# battery_brick_2_12.net
KiCad netlist of a schematic drawn in EAGLE
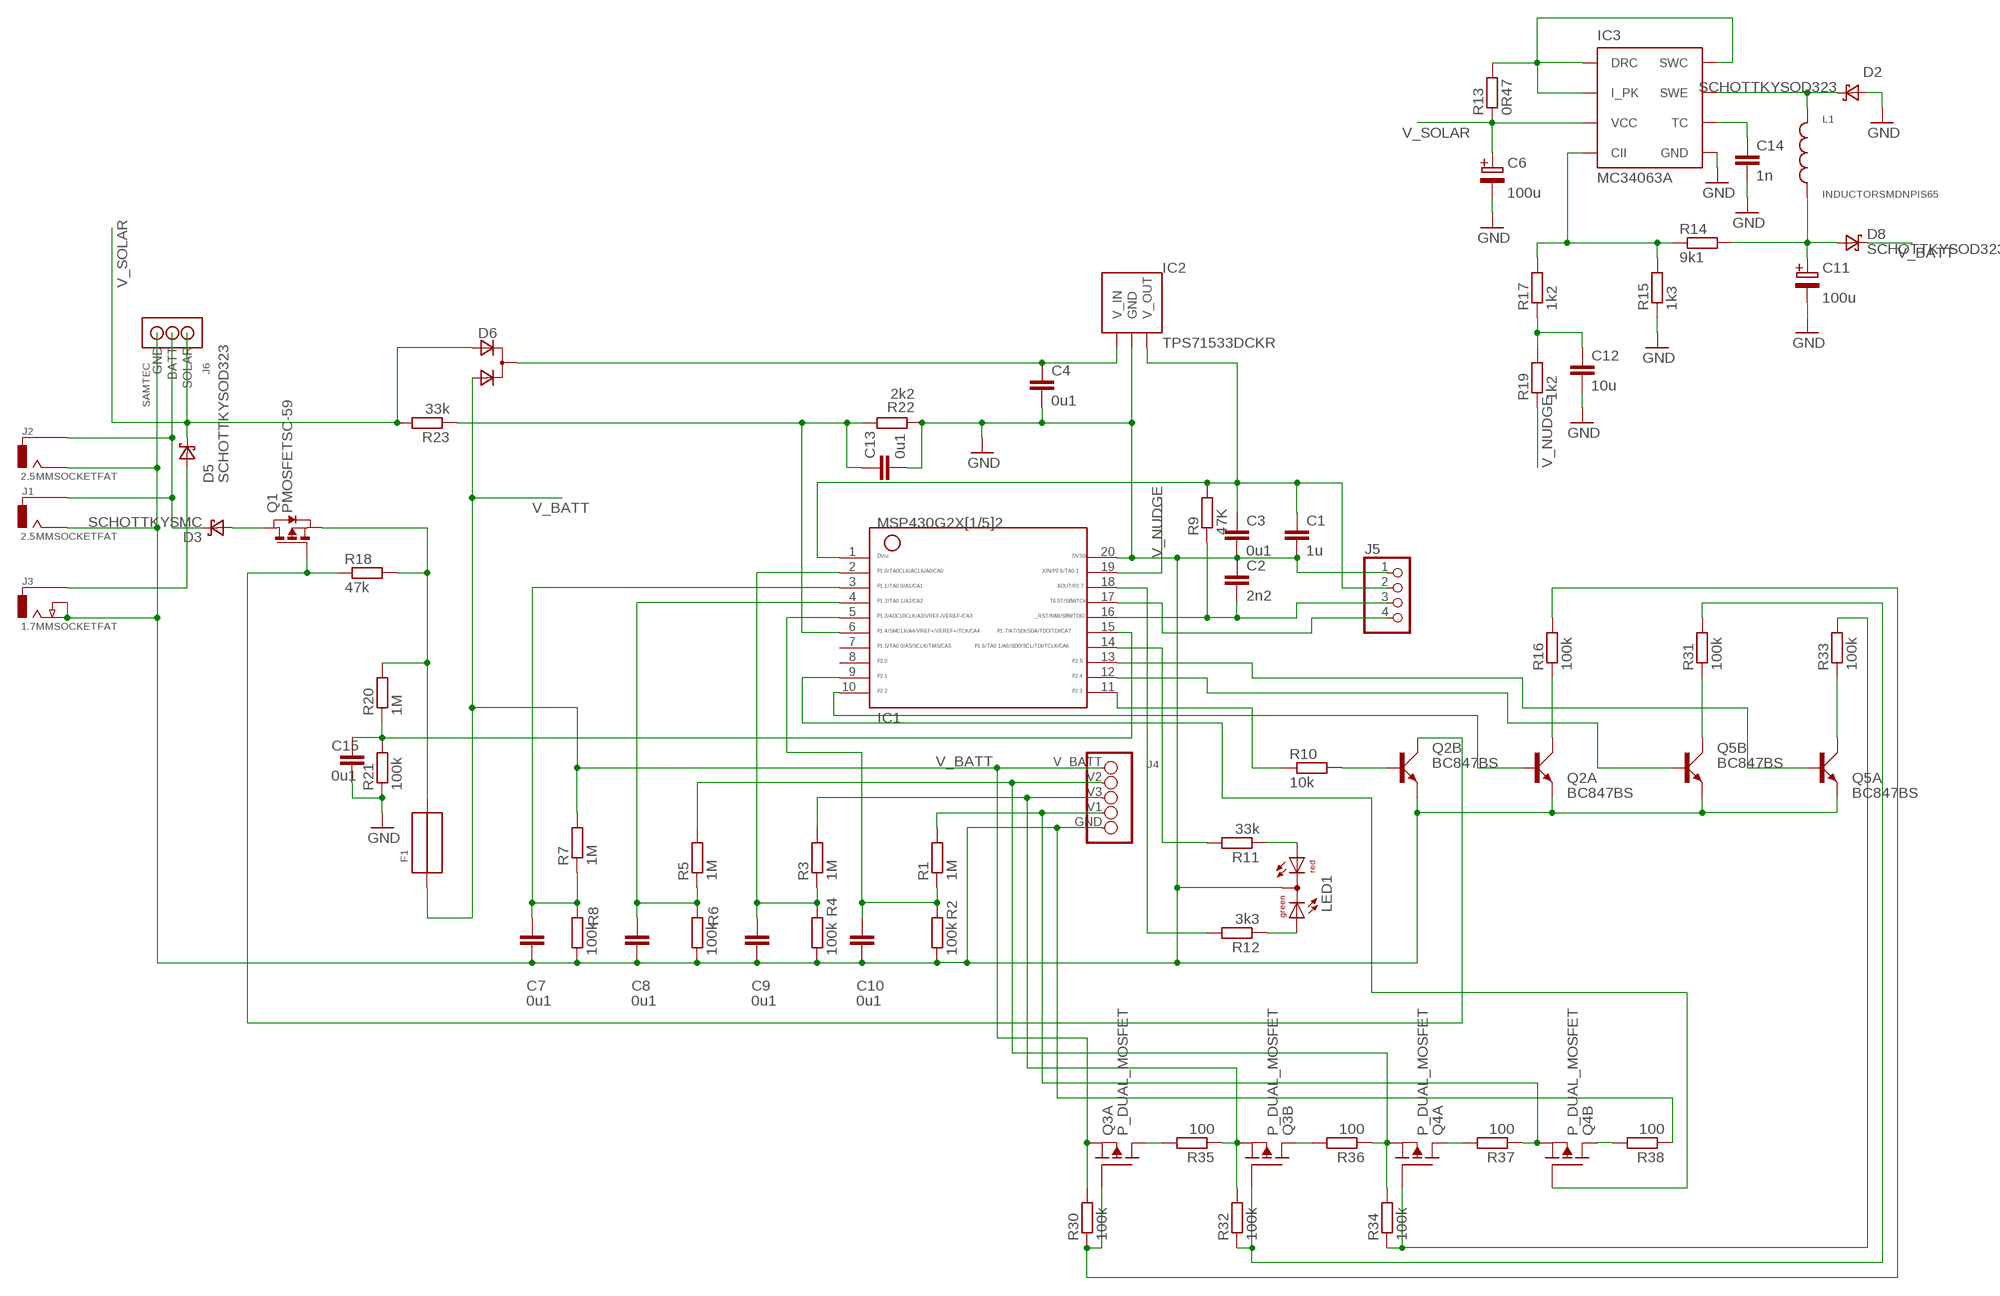
[diagram p0: schematic, sheet 1]

(export (version "E")
  (design (tool "Eeschema 10.0.6"))
  (components
    (comp (ref "C1")
      (value "1u")
      (footprint "eagle-import:C0603K")
      (libsource (lib "eagle-import") (part "C-EUC0603K"))
    )
    (comp (ref "C2")
      (value "2n2")
      (footprint "eagle-import:C0603K")
      (libsource (lib "eagle-import") (part "C-EUC0603K"))
    )
    (comp (ref "C3")
      (value "0u1")
      (footprint "eagle-import:C0603K")
      (libsource (lib "eagle-import") (part "C-EUC0603K"))
    )
    (comp (ref "C4")
      (value "0u1")
      (footprint "eagle-import:C0603")
      (libsource (lib "eagle-import") (part "C-EUC0603"))
    )
    (comp (ref "C6")
      (value "100u")
      (footprint "eagle-import:CAPCANVZH101")
      (libsource (lib "eagle-import") (part "ELEC_CAP_CAN6VZH101"))
    )
    (comp (ref "C7")
      (value "0u1")
      (footprint "eagle-import:C0603")
      (libsource (lib "eagle-import") (part "C-EUC0603"))
    )
    (comp (ref "C8")
      (value "0u1")
      (footprint "eagle-import:C0603")
      (libsource (lib "eagle-import") (part "C-EUC0603"))
    )
    (comp (ref "C9")
      (value "0u1")
      (footprint "eagle-import:C0603")
      (libsource (lib "eagle-import") (part "C-EUC0603"))
    )
    (comp (ref "C10")
      (value "0u1")
      (footprint "eagle-import:C0603")
      (libsource (lib "eagle-import") (part "C-EUC0603"))
    )
    (comp (ref "C11")
      (value "100u")
      (footprint "eagle-import:CAPCANVZH101")
      (libsource (lib "eagle-import") (part "ELEC_CAP_CAN6VZH101"))
    )
    (comp (ref "C12")
      (value "10u")
      (footprint "eagle-import:C2012")
      (libsource (lib "eagle-import") (part "C-EUC2012"))
    )
    (comp (ref "C13")
      (value "0u1")
      (footprint "eagle-import:C0603")
      (libsource (lib "eagle-import") (part "C-EUC0603"))
    )
    (comp (ref "C14")
      (value "1n")
      (footprint "eagle-import:C0603")
      (libsource (lib "eagle-import") (part "C-EUC0603"))
    )
    (comp (ref "C15")
      (value "0u1")
      (footprint "eagle-import:C0603")
      (libsource (lib "eagle-import") (part "C-EUC0603"))
    )
    (comp (ref "D2")
      (value "SCHOTTKYSOD323")
      (footprint "eagle-import:SOD323")
      (libsource (lib "eagle-import") (part "SCHOTTKYSOD323"))
    )
    (comp (ref "D3")
      (value "SCHOTTKYSMC")
      (footprint "eagle-import:SMC")
      (libsource (lib "eagle-import") (part "SCHOTTKYSMC"))
    )
    (comp (ref "D5")
      (value "SCHOTTKYSOD323")
      (footprint "eagle-import:SOD323")
      (libsource (lib "eagle-import") (part "SCHOTTKYSOD323"))
    )
    (comp (ref "D6")
      (value "D_2ASOT323")
      (footprint "eagle-import:SOT323")
      (libsource (lib "eagle-import") (part "D_2ASOT323"))
    )
    (comp (ref "D8")
      (value "SCHOTTKYSOD323")
      (footprint "eagle-import:SOD323")
      (libsource (lib "eagle-import") (part "SCHOTTKYSOD323"))
    )
    (comp (ref "F1")
      (value "FUSE")
      (footprint "eagle-import:1812")
      (libsource (lib "eagle-import") (part "FUSE"))
    )
    (comp (ref "IC1")
      (value "G2X[1/5]2---PW20")
      (footprint "eagle-import:PW20")
      (libsource (lib "eagle-import") (part "G2X[1/5]2---PW20"))
    )
    (comp (ref "IC2")
      (value "TPS71533DCKR")
      (footprint "eagle-import:SC70-5")
      (libsource (lib "eagle-import") (part "TPS71533DCKR"))
    )
    (comp (ref "IC3")
      (value "MC34063A")
      (footprint "eagle-import:SOIC8")
      (libsource (lib "eagle-import") (part "MC34063A"))
    )
    (comp (ref "J1")
      (value "2.5MMSOCKETFAT")
      (footprint "eagle-import:2.5MMSOCKET-OBLONGFAT")
      (libsource (lib "eagle-import") (part "2.5MMSOCKETFAT"))
    )
    (comp (ref "J2")
      (value "2.5MMSOCKETFAT")
      (footprint "eagle-import:2.5MMSOCKET-OBLONGFAT")
      (libsource (lib "eagle-import") (part "2.5MMSOCKETFAT"))
    )
    (comp (ref "J3")
      (value "1.7MMSOCKETFAT")
      (footprint "eagle-import:1.7MMSOCKET-OBLONGFAT")
      (libsource (lib "eagle-import") (part "1.7MMSOCKETFAT"))
    )
    (comp (ref "J4")
      (value "S5B-PH-K-S")
      (footprint "eagle-import:S5B-PH-K-S")
      (libsource (lib "eagle-import") (part "S5B-PH-K-S"))
    )
    (comp (ref "J5")
      (value "PINHD-1X4")
      (footprint "eagle-import:1X04")
      (libsource (lib "eagle-import") (part "PINHD-1X4"))
    )
    (comp (ref "J6")
      (value "SAMTEC")
      (footprint "eagle-import:SAMTEC")
      (libsource (lib "eagle-import") (part "SAMTEC"))
    )
    (comp (ref "L1")
      (value "INDUCTORSMDNPIS65")
      (footprint "eagle-import:INDUCTOR_NPIS65")
      (libsource (lib "eagle-import") (part "INDUCTORSMDNPIS65"))
    )
    (comp (ref "LED1")
      (value "DUOLED5MM")
      (footprint "eagle-import:DUOLED5MM")
      (libsource (lib "eagle-import") (part "DUOLED5MM"))
    )
    (comp (ref "Q1")
      (value "PMOSFETSC-59")
      (footprint "eagle-import:SC-59")
      (libsource (lib "eagle-import") (part "PMOSFETSC-59"))
    )
    (comp (ref "Q2")
      (value "BC847BS")
      (footprint "eagle-import:SOT363_PHILIPS")
      (libsource (lib "eagle-import") (part "BC847BS"))
    )
    (comp (ref "Q3")
      (value "P_DUAL_MOSFET")
      (footprint "eagle-import:SOT666")
      (libsource (lib "eagle-import") (part "P_DUAL_MOSFET"))
    )
    (comp (ref "Q4")
      (value "P_DUAL_MOSFET")
      (footprint "eagle-import:SOT666")
      (libsource (lib "eagle-import") (part "P_DUAL_MOSFET"))
    )
    (comp (ref "Q5")
      (value "BC847BS")
      (footprint "eagle-import:SOT363_PHILIPS")
      (libsource (lib "eagle-import") (part "BC847BS"))
    )
    (comp (ref "R1")
      (value "1M")
      (footprint "eagle-import:R0805")
      (libsource (lib "eagle-import") (part "R-EU_R0805"))
    )
    (comp (ref "R2")
      (value "100k")
      (footprint "eagle-import:R0805")
      (libsource (lib "eagle-import") (part "resistor_R-EU_R0805"))
    )
    (comp (ref "R3")
      (value "1M")
      (footprint "eagle-import:R0805")
      (libsource (lib "eagle-import") (part "R-EU_R0805"))
    )
    (comp (ref "R4")
      (value "100k")
      (footprint "eagle-import:R0805")
      (libsource (lib "eagle-import") (part "resistor_R-EU_R0805"))
    )
    (comp (ref "R5")
      (value "1M")
      (footprint "eagle-import:R0805")
      (libsource (lib "eagle-import") (part "R-EU_R0805"))
    )
    (comp (ref "R6")
      (value "100k")
      (footprint "eagle-import:R0805")
      (libsource (lib "eagle-import") (part "resistor_R-EU_R0805"))
    )
    (comp (ref "R7")
      (value "1M")
      (footprint "eagle-import:R0805")
      (libsource (lib "eagle-import") (part "R-EU_R0805"))
    )
    (comp (ref "R8")
      (value "100k")
      (footprint "eagle-import:R0805")
      (libsource (lib "eagle-import") (part "resistor_R-EU_R0805"))
    )
    (comp (ref "R9")
      (value "47K")
      (footprint "eagle-import:R0603")
      (libsource (lib "eagle-import") (part "R-EU_R0603"))
    )
    (comp (ref "R10")
      (value "10k")
      (footprint "eagle-import:R0603")
      (libsource (lib "eagle-import") (part "R-EU_R0603"))
    )
    (comp (ref "R11")
      (value "33k")
      (footprint "eagle-import:R0603")
      (libsource (lib "eagle-import") (part "resistor_R-EU_R0603"))
    )
    (comp (ref "R12")
      (value "3k3")
      (footprint "eagle-import:R0603")
      (libsource (lib "eagle-import") (part "resistor_R-EU_R0603"))
    )
    (comp (ref "R13")
      (value "0R47")
      (footprint "eagle-import:R1206")
      (libsource (lib "eagle-import") (part "R-EU_R1206"))
    )
    (comp (ref "R14")
      (value "9k1")
      (footprint "eagle-import:R0603")
      (libsource (lib "eagle-import") (part "R-EU_R0603"))
    )
    (comp (ref "R15")
      (value "1k3")
      (footprint "eagle-import:R0603")
      (libsource (lib "eagle-import") (part "R-EU_R0603"))
    )
    (comp (ref "R16")
      (value "100k")
      (footprint "eagle-import:R0603")
      (libsource (lib "eagle-import") (part "resistor_R-EU_R0603"))
    )
    (comp (ref "R17")
      (value "1k2")
      (footprint "eagle-import:R0603")
      (libsource (lib "eagle-import") (part "R-EU_R0603"))
    )
    (comp (ref "R18")
      (value "47k")
      (footprint "eagle-import:R0603")
      (libsource (lib "eagle-import") (part "R-EU_R0603"))
    )
    (comp (ref "R19")
      (value "1k2")
      (footprint "eagle-import:R0603")
      (libsource (lib "eagle-import") (part "R-EU_R0603"))
    )
    (comp (ref "R20")
      (value "1M")
      (footprint "eagle-import:R0603")
      (libsource (lib "eagle-import") (part "R-EU_R0603"))
    )
    (comp (ref "R21")
      (value "100k")
      (footprint "eagle-import:R0603")
      (libsource (lib "eagle-import") (part "resistor_R-EU_R0603"))
    )
    (comp (ref "R22")
      (value "2k2")
      (footprint "eagle-import:R0603")
      (libsource (lib "eagle-import") (part "resistor_R-EU_R0603"))
    )
    (comp (ref "R23")
      (value "33k")
      (footprint "eagle-import:R0603")
      (libsource (lib "eagle-import") (part "resistor_R-EU_R0603"))
    )
    (comp (ref "R30")
      (value "100k")
      (footprint "eagle-import:R0603")
      (libsource (lib "eagle-import") (part "resistor_R-EU_R0603"))
    )
    (comp (ref "R31")
      (value "100k")
      (footprint "eagle-import:R0603")
      (libsource (lib "eagle-import") (part "resistor_R-EU_R0603"))
    )
    (comp (ref "R32")
      (value "100k")
      (footprint "eagle-import:R0603")
      (libsource (lib "eagle-import") (part "resistor_R-EU_R0603"))
    )
    (comp (ref "R33")
      (value "100k")
      (footprint "eagle-import:R0603")
      (libsource (lib "eagle-import") (part "resistor_R-EU_R0603"))
    )
    (comp (ref "R34")
      (value "100k")
      (footprint "eagle-import:R0603")
      (libsource (lib "eagle-import") (part "resistor_R-EU_R0603"))
    )
    (comp (ref "R35")
      (value "100")
      (footprint "eagle-import:M1206")
      (libsource (lib "eagle-import") (part "R-EU_M1206"))
    )
    (comp (ref "R36")
      (value "100")
      (footprint "eagle-import:M1206")
      (libsource (lib "eagle-import") (part "R-EU_M1206"))
    )
    (comp (ref "R37")
      (value "100")
      (footprint "eagle-import:M1206")
      (libsource (lib "eagle-import") (part "R-EU_M1206"))
    )
    (comp (ref "R38")
      (value "100")
      (footprint "eagle-import:M1206")
      (libsource (lib "eagle-import") (part "R-EU_M1206"))
    )
  )
  (nets
    (net (code "1") (name "/V_BATT") (class "Default")
      (node (ref "D6") (pin "3") (pinfunction "A2_3") (pintype "passive"))
      (node (ref "D8") (pin "CATHODE") (pinfunction "CATHODE_CATHODE") (pintype "passive"))
      (node (ref "F1") (pin "1") (pinfunction "P$1_1") (pintype "bidirectional"))
      (node (ref "J4") (pin "V_BATT") (pinfunction "V_BATT_V_BATT") (pintype "input"))
      (node (ref "Q3") (pin "1") (pinfunction "S_1") (pintype "passive"))
      (node (ref "R30") (pin "2") (pinfunction "2_2") (pintype "passive"))
      (node (ref "R7") (pin "2") (pinfunction "2_2") (pintype "passive"))
    )
    (net (code "2") (name "/V_NUDGE") (class "Default")
      (node (ref "IC1") (pin "19") (pinfunction "19_19") (pintype "bidirectional"))
      (node (ref "R19") (pin "1") (pinfunction "1_1") (pintype "passive"))
    )
    (net (code "3") (name "/V_SOLAR") (class "Default")
      (node (ref "C6") (pin "+VE") (pinfunction "P$1+_+VE") (pintype "bidirectional"))
      (node (ref "D5") (pin "CATHODE") (pinfunction "CATHODE_CATHODE") (pintype "passive"))
      (node (ref "D6") (pin "2") (pinfunction "A1_2") (pintype "passive"))
      (node (ref "IC3") (pin "VCC") (pinfunction "VCC_VCC") (pintype "input"))
      (node (ref "J6") (pin "SOLAR") (pinfunction "SOLAR_SOLAR") (pintype "bidirectional"))
      (node (ref "R13") (pin "1") (pinfunction "1_1") (pintype "passive"))
      (node (ref "R23") (pin "2") (pinfunction "2_2") (pintype "passive"))
    )
    (net (code "4") (name "GND") (class "Default")
      (node (ref "C1") (pin "2") (pinfunction "2_2") (pintype "passive"))
      (node (ref "C10") (pin "2") (pinfunction "2_2") (pintype "passive"))
      (node (ref "C11") (pin "-VE") (pinfunction "P$2_-VE") (pintype "bidirectional"))
      (node (ref "C12") (pin "2") (pinfunction "2_2") (pintype "passive"))
      (node (ref "C13") (pin "2") (pinfunction "2_2") (pintype "passive"))
      (node (ref "C14") (pin "2") (pinfunction "2_2") (pintype "passive"))
      (node (ref "C15") (pin "2") (pinfunction "2_2") (pintype "passive"))
      (node (ref "C2") (pin "1") (pinfunction "1_1") (pintype "passive"))
      (node (ref "C3") (pin "2") (pinfunction "2_2") (pintype "passive"))
      (node (ref "C4") (pin "2") (pinfunction "2_2") (pintype "passive"))
      (node (ref "C6") (pin "-VE") (pinfunction "P$2_-VE") (pintype "bidirectional"))
      (node (ref "C7") (pin "2") (pinfunction "2_2") (pintype "passive"))
      (node (ref "C8") (pin "2") (pinfunction "2_2") (pintype "passive"))
      (node (ref "C9") (pin "2") (pinfunction "2_2") (pintype "passive"))
      (node (ref "D2") (pin "ANODE") (pinfunction "ANODE_ANODE") (pintype "passive"))
      (node (ref "IC1") (pin "20") (pinfunction "20_20") (pintype "bidirectional"))
      (node (ref "IC2") (pin "GND") (pinfunction "GND_GND") (pintype "bidirectional"))
      (node (ref "IC3") (pin "GND") (pinfunction "GND_GND") (pintype "power_in"))
      (node (ref "J1") (pin "-VE") (pinfunction "-VE_-VE") (pintype "bidirectional"))
      (node (ref "J2") (pin "-VE") (pinfunction "-VE_-VE") (pintype "bidirectional"))
      (node (ref "J3") (pin "-VE") (pinfunction "-VE_-VE") (pintype "bidirectional"))
      (node (ref "J3") (pin "P$3") (pinfunction "P$1_P$3") (pintype "bidirectional"))
      (node (ref "J4") (pin "GND") (pinfunction "GND_GND") (pintype "input"))
      (node (ref "J5") (pin "1") (pinfunction "1_1") (pintype "passive"))
      (node (ref "J6") (pin "GND") (pinfunction "GND_GND") (pintype "bidirectional"))
      (node (ref "LED1") (pin "K") (pinfunction "C_K") (pintype "passive"))
      (node (ref "Q2") (pin "1") (pinfunction "E_1") (pintype "passive"))
      (node (ref "Q2") (pin "4") (pinfunction "E_4") (pintype "passive"))
      (node (ref "Q5") (pin "1") (pinfunction "E_1") (pintype "passive"))
      (node (ref "Q5") (pin "4") (pinfunction "E_4") (pintype "passive"))
      (node (ref "R15") (pin "1") (pinfunction "1_1") (pintype "passive"))
      (node (ref "R2") (pin "1") (pinfunction "1_1") (pintype "passive"))
      (node (ref "R21") (pin "1") (pinfunction "1_1") (pintype "passive"))
      (node (ref "R22") (pin "1") (pinfunction "1_1") (pintype "passive"))
      (node (ref "R38") (pin "1") (pinfunction "1_1") (pintype "passive"))
      (node (ref "R4") (pin "1") (pinfunction "1_1") (pintype "passive"))
      (node (ref "R6") (pin "1") (pinfunction "1_1") (pintype "passive"))
      (node (ref "R8") (pin "1") (pinfunction "1_1") (pintype "passive"))
    )
    (net (code "5") (name "Net-(C2-Pad2)") (class "Default")
      (node (ref "C2") (pin "2") (pinfunction "2_2") (pintype "passive"))
      (node (ref "IC1") (pin "16") (pinfunction "16_16") (pintype "bidirectional"))
      (node (ref "J5") (pin "3") (pinfunction "3_3") (pintype "passive"))
      (node (ref "R9") (pin "1") (pinfunction "1_1") (pintype "passive"))
    )
    (net (code "6") (name "Net-(C7-Pad1)") (class "Default")
      (node (ref "C7") (pin "1") (pinfunction "1_1") (pintype "passive"))
      (node (ref "IC1") (pin "3") (pinfunction "3_3") (pintype "bidirectional"))
      (node (ref "R7") (pin "1") (pinfunction "1_1") (pintype "passive"))
      (node (ref "R8") (pin "2") (pinfunction "2_2") (pintype "passive"))
    )
    (net (code "7") (name "Net-(C8-Pad1)") (class "Default")
      (node (ref "C8") (pin "1") (pinfunction "1_1") (pintype "passive"))
      (node (ref "IC1") (pin "4") (pinfunction "4_4") (pintype "bidirectional"))
      (node (ref "R5") (pin "1") (pinfunction "1_1") (pintype "passive"))
      (node (ref "R6") (pin "2") (pinfunction "2_2") (pintype "passive"))
    )
    (net (code "8") (name "Net-(C9-Pad1)") (class "Default")
      (node (ref "C9") (pin "1") (pinfunction "1_1") (pintype "passive"))
      (node (ref "IC1") (pin "2") (pinfunction "2_2") (pintype "bidirectional"))
      (node (ref "R3") (pin "1") (pinfunction "1_1") (pintype "passive"))
      (node (ref "R4") (pin "2") (pinfunction "2_2") (pintype "passive"))
    )
    (net (code "9") (name "Net-(C10-Pad1)") (class "Default")
      (node (ref "C10") (pin "1") (pinfunction "1_1") (pintype "passive"))
      (node (ref "IC1") (pin "5") (pinfunction "5_5") (pintype "bidirectional"))
      (node (ref "R1") (pin "1") (pinfunction "1_1") (pintype "passive"))
      (node (ref "R2") (pin "2") (pinfunction "2_2") (pintype "passive"))
    )
    (net (code "10") (name "Net-(C11-P$1+)") (class "Default")
      (node (ref "C11") (pin "+VE") (pinfunction "P$1+_+VE") (pintype "bidirectional"))
      (node (ref "D8") (pin "ANODE") (pinfunction "ANODE_ANODE") (pintype "passive"))
      (node (ref "L1") (pin "P$2") (pinfunction "P$2_P$2") (pintype "bidirectional"))
      (node (ref "R14") (pin "2") (pinfunction "2_2") (pintype "passive"))
    )
    (net (code "11") (name "Net-(C12-Pad1)") (class "Default")
      (node (ref "C12") (pin "1") (pinfunction "1_1") (pintype "passive"))
      (node (ref "R17") (pin "1") (pinfunction "1_1") (pintype "passive"))
      (node (ref "R19") (pin "2") (pinfunction "2_2") (pintype "passive"))
    )
    (net (code "12") (name "Net-(C13-Pad1)") (class "Default")
      (node (ref "C13") (pin "1") (pinfunction "1_1") (pintype "passive"))
      (node (ref "IC1") (pin "6") (pinfunction "6_6") (pintype "bidirectional"))
      (node (ref "R22") (pin "2") (pinfunction "2_2") (pintype "passive"))
      (node (ref "R23") (pin "1") (pinfunction "1_1") (pintype "passive"))
    )
    (net (code "13") (name "Net-(C14-Pad1)") (class "Default")
      (node (ref "C14") (pin "1") (pinfunction "1_1") (pintype "passive"))
      (node (ref "IC3") (pin "TC") (pinfunction "TC_TC") (pintype "open_collector"))
    )
    (net (code "14") (name "Net-(C15-Pad1)") (class "Default")
      (node (ref "C15") (pin "1") (pinfunction "1_1") (pintype "passive"))
      (node (ref "IC1") (pin "15") (pinfunction "15_15") (pintype "bidirectional"))
      (node (ref "R20") (pin "1") (pinfunction "1_1") (pintype "passive"))
      (node (ref "R21") (pin "2") (pinfunction "2_2") (pintype "passive"))
    )
    (net (code "15") (name "Net-(D2-PadCATHODE)") (class "Default")
      (node (ref "D2") (pin "CATHODE") (pinfunction "CATHODE_CATHODE") (pintype "passive"))
      (node (ref "IC3") (pin "SWE") (pinfunction "SWE_SWE") (pintype "open_collector"))
      (node (ref "L1") (pin "P$1") (pinfunction "P$1_P$1") (pintype "bidirectional"))
    )
    (net (code "16") (name "Net-(D3-PadANODE)") (class "Default")
      (node (ref "D3") (pin "ANODE") (pinfunction "ANODE_ANODE") (pintype "passive"))
      (node (ref "Q1") (pin "D") (pinfunction "D_D") (pintype "passive"))
    )
    (net (code "17") (name "Net-(D3-PadCATHODE)") (class "Default")
      (node (ref "D3") (pin "CATHODE") (pinfunction "CATHODE_CATHODE") (pintype "passive"))
      (node (ref "J1") (pin "+VE") (pinfunction "+VE_+VE") (pintype "bidirectional"))
      (node (ref "J2") (pin "+VE") (pinfunction "+VE_+VE") (pintype "bidirectional"))
      (node (ref "J6") (pin "BATT") (pinfunction "BATT_BATT") (pintype "bidirectional"))
    )
    (net (code "18") (name "Net-(D5-PadANODE)") (class "Default")
      (node (ref "D5") (pin "ANODE") (pinfunction "ANODE_ANODE") (pintype "passive"))
      (node (ref "J3") (pin "+VE") (pinfunction "+VE_+VE") (pintype "bidirectional"))
    )
    (net (code "19") (name "Net-(D6-C)") (class "Default")
      (node (ref "C4") (pin "1") (pinfunction "1_1") (pintype "passive"))
      (node (ref "D6") (pin "1") (pinfunction "C_1") (pintype "passive"))
      (node (ref "IC2") (pin "IN") (pinfunction "V_IN_IN") (pintype "bidirectional"))
    )
    (net (code "20") (name "Net-(F1-P$2)") (class "Default")
      (node (ref "F1") (pin "2") (pinfunction "P$2_2") (pintype "bidirectional"))
      (node (ref "Q1") (pin "S") (pinfunction "S_S") (pintype "passive"))
      (node (ref "R18") (pin "2") (pinfunction "2_2") (pintype "passive"))
      (node (ref "R20") (pin "2") (pinfunction "2_2") (pintype "passive"))
    )
    (net (code "21") (name "Net-(IC1-Pad11)") (class "Default")
      (node (ref "IC1") (pin "11") (pinfunction "11_11") (pintype "bidirectional"))
      (node (ref "R10") (pin "1") (pinfunction "1_1") (pintype "passive"))
    )
    (net (code "22") (name "Net-(IC1-Pad14)") (class "Default")
      (node (ref "IC1") (pin "14") (pinfunction "14_14") (pintype "bidirectional"))
      (node (ref "R11") (pin "2") (pinfunction "2_2") (pintype "passive"))
    )
    (net (code "23") (name "Net-(IC1-Pad17)") (class "Default")
      (node (ref "IC1") (pin "17") (pinfunction "17_17") (pintype "bidirectional"))
      (node (ref "J5") (pin "4") (pinfunction "4_4") (pintype "passive"))
    )
    (net (code "24") (name "Net-(IC1-Pad18)") (class "Default")
      (node (ref "IC1") (pin "18") (pinfunction "18_18") (pintype "bidirectional"))
      (node (ref "R12") (pin "2") (pinfunction "2_2") (pintype "passive"))
    )
    (net (code "25") (name "Net-(IC2-V_OUT)") (class "Default")
      (node (ref "C1") (pin "1") (pinfunction "1_1") (pintype "passive"))
      (node (ref "C3") (pin "1") (pinfunction "1_1") (pintype "passive"))
      (node (ref "IC1") (pin "1") (pinfunction "1_1") (pintype "bidirectional"))
      (node (ref "IC2") (pin "OUT") (pinfunction "V_OUT_OUT") (pintype "bidirectional"))
      (node (ref "J5") (pin "2") (pinfunction "2_2") (pintype "passive"))
      (node (ref "R9") (pin "2") (pinfunction "2_2") (pintype "passive"))
    )
    (net (code "26") (name "Net-(IC3-PadCII)") (class "Default")
      (node (ref "IC3") (pin "CII") (pinfunction "CII_CII") (pintype "input"))
      (node (ref "R14") (pin "1") (pinfunction "1_1") (pintype "passive"))
      (node (ref "R15") (pin "2") (pinfunction "2_2") (pintype "passive"))
      (node (ref "R17") (pin "2") (pinfunction "2_2") (pintype "passive"))
    )
    (net (code "27") (name "Net-(IC3-PadDRC)") (class "Default")
      (node (ref "IC3") (pin "DRC") (pinfunction "DRC_DRC") (pintype "output"))
      (node (ref "IC3") (pin "I_PK") (pinfunction "I_PK_I_PK") (pintype "input"))
      (node (ref "IC3") (pin "SWC") (pinfunction "SWC_SWC") (pintype "power_in"))
      (node (ref "R13") (pin "2") (pinfunction "2_2") (pintype "passive"))
    )
    (net (code "28") (name "Net-(LED1-PadAG)") (class "Default")
      (node (ref "LED1") (pin "AG") (pinfunction "AG_AG") (pintype "passive"))
      (node (ref "R12") (pin "1") (pinfunction "1_1") (pintype "passive"))
    )
    (net (code "29") (name "Net-(LED1-PadAR)") (class "Default")
      (node (ref "LED1") (pin "AR") (pinfunction "AR_AR") (pintype "passive"))
      (node (ref "R11") (pin "1") (pinfunction "1_1") (pintype "passive"))
    )
    (net (code "30") (name "Net-(Q2A-B)") (class "Default")
      (node (ref "IC1") (pin "10") (pinfunction "10_10") (pintype "bidirectional"))
      (node (ref "Q2") (pin "2") (pinfunction "B_2") (pintype "passive"))
    )
    (net (code "31") (name "Net-(Q2A-C)") (class "Default")
      (node (ref "Q2") (pin "6") (pinfunction "C_6") (pintype "passive"))
      (node (ref "R16") (pin "1") (pinfunction "1_1") (pintype "passive"))
    )
    (net (code "32") (name "Net-(Q2B-B)") (class "Default")
      (node (ref "Q2") (pin "5") (pinfunction "B_5") (pintype "passive"))
      (node (ref "R10") (pin "2") (pinfunction "2_2") (pintype "passive"))
    )
    (net (code "33") (name "Net-(Q2B-C)") (class "Default")
      (node (ref "Q1") (pin "G") (pinfunction "G_G") (pintype "passive"))
      (node (ref "Q2") (pin "3") (pinfunction "C_3") (pintype "passive"))
      (node (ref "R18") (pin "1") (pinfunction "1_1") (pintype "passive"))
    )
    (net (code "34") (name "Net-(Q3A-D)") (class "Default")
      (node (ref "Q3") (pin "6") (pinfunction "D_6") (pintype "passive"))
      (node (ref "R35") (pin "2") (pinfunction "2_2") (pintype "passive"))
    )
    (net (code "35") (name "Net-(Q3A-G)") (class "Default")
      (node (ref "Q3") (pin "2") (pinfunction "G_2") (pintype "passive"))
      (node (ref "R16") (pin "2") (pinfunction "2_2") (pintype "passive"))
      (node (ref "R30") (pin "1") (pinfunction "1_1") (pintype "passive"))
    )
    (net (code "36") (name "Net-(Q3B-D)") (class "Default")
      (node (ref "Q3") (pin "3") (pinfunction "D_3") (pintype "passive"))
      (node (ref "R36") (pin "2") (pinfunction "2_2") (pintype "passive"))
    )
    (net (code "37") (name "Net-(Q3B-G)") (class "Default")
      (node (ref "Q3") (pin "5") (pinfunction "G_5") (pintype "passive"))
      (node (ref "R31") (pin "2") (pinfunction "2_2") (pintype "passive"))
      (node (ref "R32") (pin "1") (pinfunction "1_1") (pintype "passive"))
    )
    (net (code "38") (name "Net-(Q3B-S)") (class "Default")
      (node (ref "J4") (pin "V3") (pinfunction "V3_V3") (pintype "input"))
      (node (ref "Q3") (pin "4") (pinfunction "S_4") (pintype "passive"))
      (node (ref "R3") (pin "2") (pinfunction "2_2") (pintype "passive"))
      (node (ref "R32") (pin "2") (pinfunction "2_2") (pintype "passive"))
      (node (ref "R35") (pin "1") (pinfunction "1_1") (pintype "passive"))
    )
    (net (code "39") (name "Net-(Q4A-D)") (class "Default")
      (node (ref "Q4") (pin "6") (pinfunction "D_6") (pintype "passive"))
      (node (ref "R37") (pin "2") (pinfunction "2_2") (pintype "passive"))
    )
    (net (code "40") (name "Net-(Q4A-G)") (class "Default")
      (node (ref "Q4") (pin "2") (pinfunction "G_2") (pintype "passive"))
      (node (ref "R33") (pin "2") (pinfunction "2_2") (pintype "passive"))
      (node (ref "R34") (pin "1") (pinfunction "1_1") (pintype "passive"))
    )
    (net (code "41") (name "Net-(Q4A-S)") (class "Default")
      (node (ref "J4") (pin "V2") (pinfunction "V2_V2") (pintype "input"))
      (node (ref "Q4") (pin "1") (pinfunction "S_1") (pintype "passive"))
      (node (ref "R34") (pin "2") (pinfunction "2_2") (pintype "passive"))
      (node (ref "R36") (pin "1") (pinfunction "1_1") (pintype "passive"))
      (node (ref "R5") (pin "2") (pinfunction "2_2") (pintype "passive"))
    )
    (net (code "42") (name "Net-(Q4B-D)") (class "Default")
      (node (ref "Q4") (pin "3") (pinfunction "D_3") (pintype "passive"))
      (node (ref "R38") (pin "2") (pinfunction "2_2") (pintype "passive"))
    )
    (net (code "43") (name "Net-(Q4B-G)") (class "Default")
      (node (ref "IC1") (pin "9") (pinfunction "9_9") (pintype "bidirectional"))
      (node (ref "Q4") (pin "5") (pinfunction "G_5") (pintype "passive"))
    )
    (net (code "44") (name "Net-(Q4B-S)") (class "Default")
      (node (ref "J4") (pin "V1") (pinfunction "V1_V1") (pintype "input"))
      (node (ref "Q4") (pin "4") (pinfunction "S_4") (pintype "passive"))
      (node (ref "R1") (pin "2") (pinfunction "2_2") (pintype "passive"))
      (node (ref "R37") (pin "1") (pinfunction "1_1") (pintype "passive"))
    )
    (net (code "45") (name "Net-(Q5A-B)") (class "Default")
      (node (ref "IC1") (pin "13") (pinfunction "13_13") (pintype "bidirectional"))
      (node (ref "Q5") (pin "2") (pinfunction "B_2") (pintype "passive"))
    )
    (net (code "46") (name "Net-(Q5A-C)") (class "Default")
      (node (ref "Q5") (pin "6") (pinfunction "C_6") (pintype "passive"))
      (node (ref "R33") (pin "1") (pinfunction "1_1") (pintype "passive"))
    )
    (net (code "47") (name "Net-(Q5B-B)") (class "Default")
      (node (ref "IC1") (pin "12") (pinfunction "12_12") (pintype "bidirectional"))
      (node (ref "Q5") (pin "5") (pinfunction "B_5") (pintype "passive"))
    )
    (net (code "48") (name "Net-(Q5B-C)") (class "Default")
      (node (ref "Q5") (pin "3") (pinfunction "C_3") (pintype "passive"))
      (node (ref "R31") (pin "1") (pinfunction "1_1") (pintype "passive"))
    )
    (net (code "49") (name "unconnected-(IC1-Pad7)") (class "Default")
      (node (ref "IC1") (pin "7") (pinfunction "7_7") (pintype "bidirectional"))
    )
    (net (code "50") (name "unconnected-(IC1-Pad8)") (class "Default")
      (node (ref "IC1") (pin "8") (pinfunction "8_8") (pintype "bidirectional"))
    )
  )
)
